# joypad.net
KiCad netlist of a schematic drawn in EAGLE
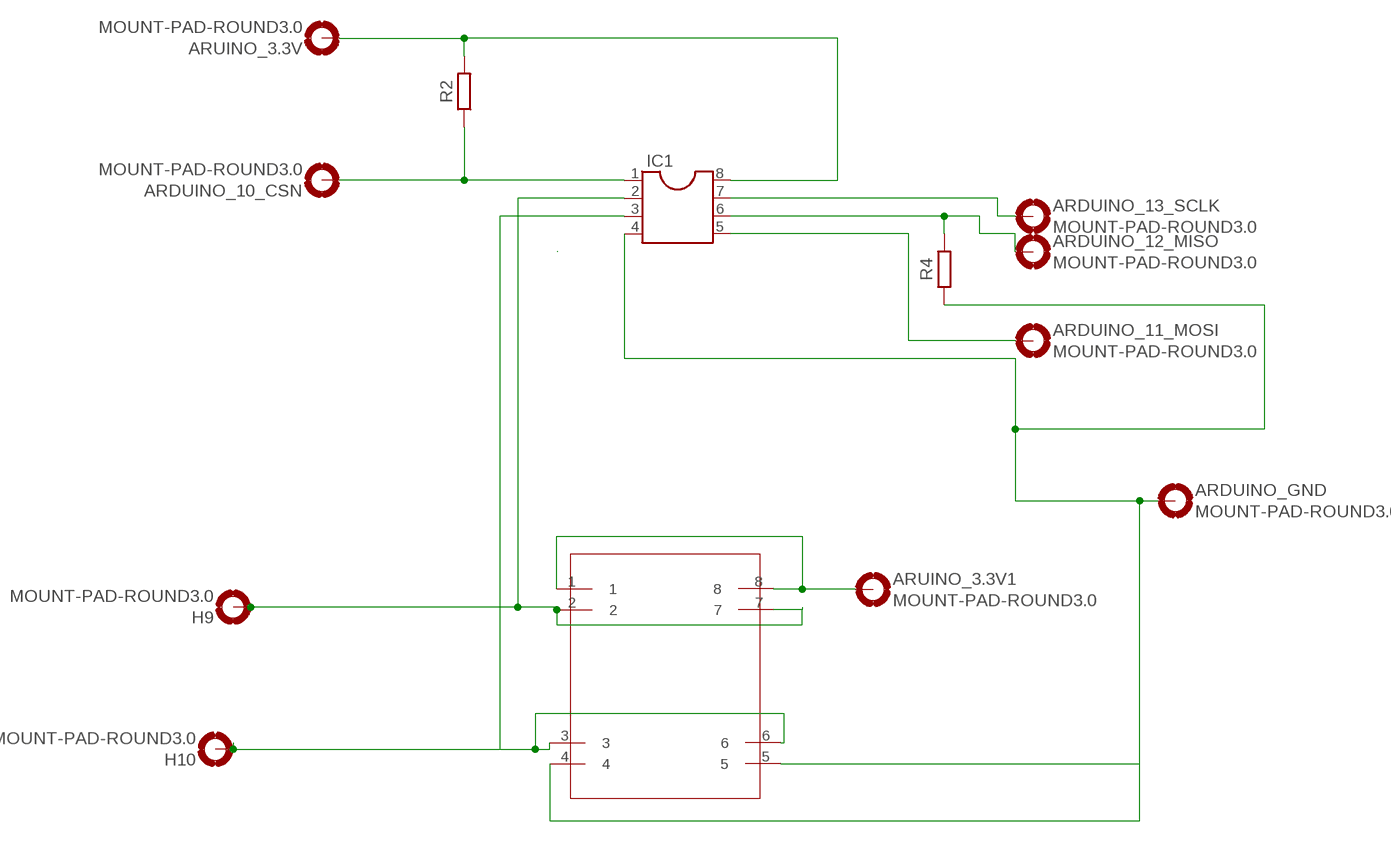
[diagram p0: schematic, sheet 1]

(export (version "E")
  (design (tool "Eeschema 10.0.6"))
  (components
    (comp (ref "ARDUINO_10_CSN")
      (value "MOUNT-PAD-ROUND3.0")
      (footprint "eagle-import:3,0-PAD")
      (libsource (lib "eagle-import") (part "MOUNT-PAD-ROUND3.0"))
    )
    (comp (ref "ARDUINO_11_MOSI")
      (value "MOUNT-PAD-ROUND3.0")
      (footprint "eagle-import:3,0-PAD")
      (libsource (lib "eagle-import") (part "MOUNT-PAD-ROUND3.0"))
    )
    (comp (ref "ARDUINO_12_MISO")
      (value "MOUNT-PAD-ROUND3.0")
      (footprint "eagle-import:3,0-PAD")
      (libsource (lib "eagle-import") (part "MOUNT-PAD-ROUND3.0"))
    )
    (comp (ref "ARDUINO_13_SCLK")
      (value "MOUNT-PAD-ROUND3.0")
      (footprint "eagle-import:3,0-PAD")
      (libsource (lib "eagle-import") (part "MOUNT-PAD-ROUND3.0"))
    )
    (comp (ref "ARDUINO_GND")
      (value "MOUNT-PAD-ROUND3.0")
      (footprint "eagle-import:3,0-PAD")
      (libsource (lib "eagle-import") (part "MOUNT-PAD-ROUND3.0"))
    )
    (comp (ref "ARUINO_3.3V")
      (value "MOUNT-PAD-ROUND3.0")
      (footprint "eagle-import:3,0-PAD")
      (libsource (lib "eagle-import") (part "MOUNT-PAD-ROUND3.0"))
    )
    (comp (ref "ARUINO_3.3V1")
      (value "MOUNT-PAD-ROUND3.0")
      (footprint "eagle-import:3,0-PAD")
      (libsource (lib "eagle-import") (part "MOUNT-PAD-ROUND3.0"))
    )
    (comp (ref "H9")
      (value "MOUNT-PAD-ROUND3.0")
      (footprint "eagle-import:3,0-PAD")
      (libsource (lib "eagle-import") (part "MOUNT-PAD-ROUND3.0"))
    )
    (comp (ref "H10")
      (value "MOUNT-PAD-ROUND3.0")
      (footprint "eagle-import:3,0-PAD")
      (libsource (lib "eagle-import") (part "MOUNT-PAD-ROUND3.0"))
    )
    (comp (ref "IC1")
      (value "DIL8")
      (footprint "eagle-import:DIL08")
      (libsource (lib "eagle-import") (part "DIL8"))
    )
    (comp (ref "R2")
      (value "R_AXIAL-7.2MM-PITCH")
      (footprint "eagle-import:RESAD724W46L381D178B")
      (libsource (lib "eagle-import") (part "RAXIAL-7.2MM-PITCH_"))
    )
    (comp (ref "R4")
      (value "R_AXIAL-7.2MM-PITCH")
      (footprint "eagle-import:RESAD724W46L381D178B")
      (libsource (lib "eagle-import") (part "RAXIAL-7.2MM-PITCH_"))
    )
    (comp (ref "U$1")
      (value "JOYSTICK")
      (footprint "eagle-import:JOYPAD")
      (libsource (lib "eagle-import") (part "JOYSTICK"))
    )
  )
  (nets
    (net (code "1") (name "Net-(ARDUINO_10_CSN-MOUNT)") (class "Default")
      (node (ref "ARDUINO_10_CSN") (pin "B3,0") (pinfunction "MOUNT_B3,0") (pintype "passive"))
      (node (ref "IC1") (pin "1") (pinfunction "1_1") (pintype "passive"))
      (node (ref "R2") (pin "1") (pinfunction "1_1") (pintype "passive"))
    )
    (net (code "2") (name "Net-(ARDUINO_11_MOSI-MOUNT)") (class "Default")
      (node (ref "ARDUINO_11_MOSI") (pin "B3,0") (pinfunction "MOUNT_B3,0") (pintype "passive"))
      (node (ref "IC1") (pin "5") (pinfunction "5_5") (pintype "passive"))
    )
    (net (code "3") (name "Net-(ARDUINO_12_MISO-MOUNT)") (class "Default")
      (node (ref "ARDUINO_12_MISO") (pin "B3,0") (pinfunction "MOUNT_B3,0") (pintype "passive"))
      (node (ref "IC1") (pin "6") (pinfunction "6_6") (pintype "passive"))
      (node (ref "R4") (pin "2") (pinfunction "2_2") (pintype "passive"))
    )
    (net (code "4") (name "Net-(ARDUINO_13_SCLK-MOUNT)") (class "Default")
      (node (ref "ARDUINO_13_SCLK") (pin "B3,0") (pinfunction "MOUNT_B3,0") (pintype "passive"))
      (node (ref "IC1") (pin "7") (pinfunction "7_7") (pintype "passive"))
    )
    (net (code "5") (name "Net-(ARDUINO_GND-MOUNT)") (class "Default")
      (node (ref "ARDUINO_GND") (pin "B3,0") (pinfunction "MOUNT_B3,0") (pintype "passive"))
      (node (ref "IC1") (pin "4") (pinfunction "4_4") (pintype "passive"))
      (node (ref "R4") (pin "1") (pinfunction "1_1") (pintype "passive"))
      (node (ref "U$1") (pin "4") (pinfunction "4_4") (pintype "bidirectional"))
      (node (ref "U$1") (pin "5") (pinfunction "5_5") (pintype "bidirectional"))
    )
    (net (code "6") (name "Net-(ARUINO_3.3V-MOUNT)") (class "Default")
      (node (ref "ARUINO_3.3V") (pin "B3,0") (pinfunction "MOUNT_B3,0") (pintype "passive"))
      (node (ref "IC1") (pin "8") (pinfunction "8_8") (pintype "passive"))
      (node (ref "R2") (pin "2") (pinfunction "2_2") (pintype "passive"))
    )
    (net (code "7") (name "Net-(ARUINO_3.3V1-MOUNT)") (class "Default")
      (node (ref "ARUINO_3.3V1") (pin "B3,0") (pinfunction "MOUNT_B3,0") (pintype "passive"))
      (node (ref "U$1") (pin "1") (pinfunction "1_1") (pintype "bidirectional"))
      (node (ref "U$1") (pin "8") (pinfunction "8_8") (pintype "bidirectional"))
    )
    (net (code "8") (name "Net-(H9-MOUNT)") (class "Default")
      (node (ref "H9") (pin "B3,0") (pinfunction "MOUNT_B3,0") (pintype "passive"))
      (node (ref "IC1") (pin "2") (pinfunction "2_2") (pintype "passive"))
      (node (ref "U$1") (pin "2") (pinfunction "2_2") (pintype "bidirectional"))
      (node (ref "U$1") (pin "7") (pinfunction "7_7") (pintype "bidirectional"))
    )
    (net (code "9") (name "Net-(H10-MOUNT)") (class "Default")
      (node (ref "H10") (pin "B3,0") (pinfunction "MOUNT_B3,0") (pintype "passive"))
      (node (ref "IC1") (pin "3") (pinfunction "3_3") (pintype "passive"))
      (node (ref "U$1") (pin "3") (pinfunction "3_3") (pintype "bidirectional"))
      (node (ref "U$1") (pin "6") (pinfunction "6_6") (pintype "bidirectional"))
    )
  )
)
